# HIVE_BOARD_DECAWAVE.net
KiCad netlist of a schematic drawn in Altium Designer
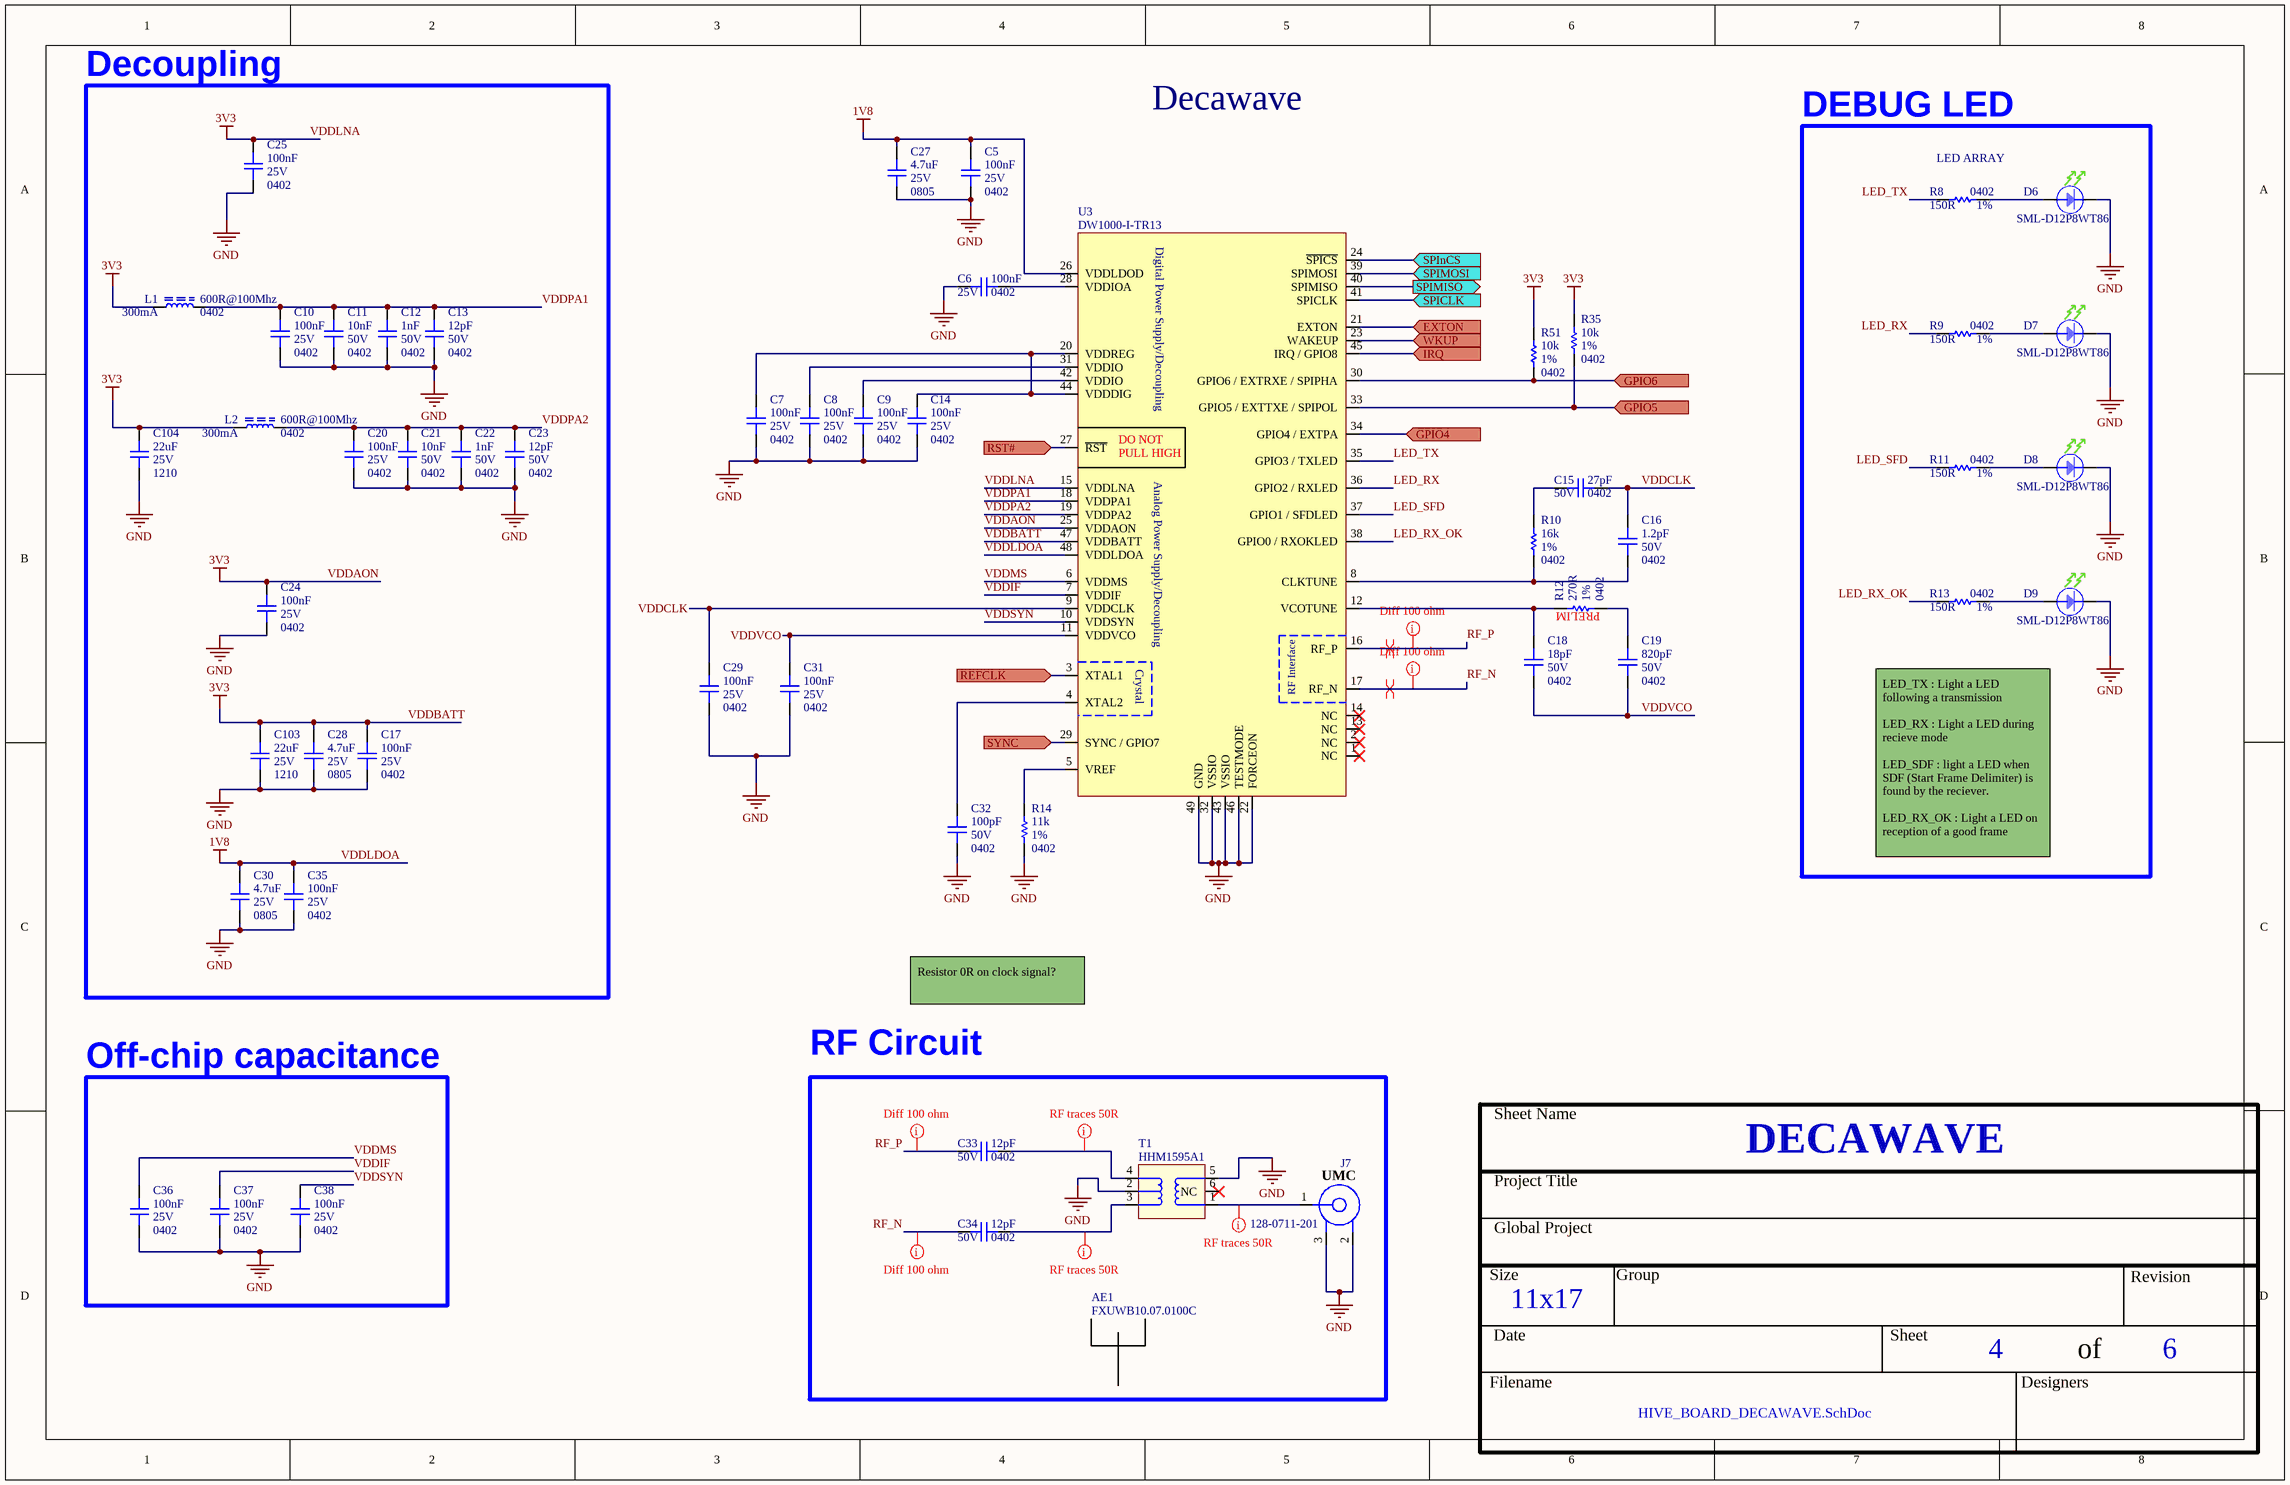
[diagram p0: HIVE_BOARD_DECAWAVE.SchDoc]

(export (version "E")
  (design (tool "Eeschema 10.0.6"))
  (components
    (comp (ref "AE1")
      (value "FXUWB10.07.0100C")
      (description "External antenna - UWB - UMCC plug")
      (fields (field (name "CREATEDBY/DATE") "Philippe Arsenault"))
      (libsource (lib "SWARMUS_LIB") (part "ANT_FXUWB10.07.0100C"))
    )
    (comp (ref "C5")
      (value "100nF")
      (footprint "GRAMS_MASTER_LIB_PCB:CAP_CER_0402")
      (description "CAP - CER 0.1µF 10% 25V X7R - 0402")
      (fields
        (field (name "TOLERANCE") "10%")
        (field (name "PACKAGE") "0402")
        (field (name "VOLTAGE RATING") "25V")
        (field (name "Comment") "CGA2B3X7R1E104K050BB")
        (field (name "CREATEDBY/DATE") "Nicolas Roy 2018-11-07")
        (field (name "VERIFIEDBY") "Nicolas V. (2019-01-22)")
      )
      (libsource (lib "GRAMS_MASTER_LIB_SCH") (part "CAP_CER_CGA2B3X7R1E104K050BB"))
    )
    (comp (ref "C6")
      (value "100nF")
      (footprint "GRAMS_MASTER_LIB_PCB:CAP_CER_0402")
      (description "CAP - CER 0.1µF 10% 25V X7R - 0402")
      (fields
        (field (name "TOLERANCE") "10%")
        (field (name "PACKAGE") "0402")
        (field (name "VOLTAGE RATING") "25V")
        (field (name "Comment") "CGA2B3X7R1E104K050BB")
        (field (name "CREATEDBY/DATE") "Nicolas Roy 2018-11-07")
        (field (name "VERIFIEDBY") "Nicolas V. (2019-01-22)")
      )
      (libsource (lib "GRAMS_MASTER_LIB_SCH") (part "CAP_CER_CGA2B3X7R1E104K050BB"))
    )
    (comp (ref "C7")
      (value "100nF")
      (footprint "GRAMS_MASTER_LIB_PCB:CAP_CER_0402")
      (description "CAP - CER 0.1µF 10% 25V X7R - 0402")
      (fields
        (field (name "TOLERANCE") "10%")
        (field (name "PACKAGE") "0402")
        (field (name "VOLTAGE RATING") "25V")
        (field (name "Comment") "CGA2B3X7R1E104K050BB")
        (field (name "CREATEDBY/DATE") "Nicolas Roy 2018-11-07")
        (field (name "VERIFIEDBY") "Nicolas V. (2019-01-22)")
      )
      (libsource (lib "GRAMS_MASTER_LIB_SCH") (part "CAP_CER_CGA2B3X7R1E104K050BB"))
    )
    (comp (ref "C8")
      (value "100nF")
      (footprint "GRAMS_MASTER_LIB_PCB:CAP_CER_0402")
      (description "CAP - CER 0.1µF 10% 25V X7R - 0402")
      (fields
        (field (name "TOLERANCE") "10%")
        (field (name "PACKAGE") "0402")
        (field (name "VOLTAGE RATING") "25V")
        (field (name "Comment") "CGA2B3X7R1E104K050BB")
        (field (name "CREATEDBY/DATE") "Nicolas Roy 2018-11-07")
        (field (name "VERIFIEDBY") "Nicolas V. (2019-01-22)")
      )
      (libsource (lib "GRAMS_MASTER_LIB_SCH") (part "CAP_CER_CGA2B3X7R1E104K050BB"))
    )
    (comp (ref "C9")
      (value "100nF")
      (footprint "GRAMS_MASTER_LIB_PCB:CAP_CER_0402")
      (description "CAP - CER 0.1µF 10% 25V X7R - 0402")
      (fields
        (field (name "TOLERANCE") "10%")
        (field (name "PACKAGE") "0402")
        (field (name "VOLTAGE RATING") "25V")
        (field (name "Comment") "CGA2B3X7R1E104K050BB")
        (field (name "CREATEDBY/DATE") "Nicolas Roy 2018-11-07")
        (field (name "VERIFIEDBY") "Nicolas V. (2019-01-22)")
      )
      (libsource (lib "GRAMS_MASTER_LIB_SCH") (part "CAP_CER_CGA2B3X7R1E104K050BB"))
    )
    (comp (ref "C10")
      (value "100nF")
      (footprint "GRAMS_MASTER_LIB_PCB:CAP_CER_0402")
      (description "CAP - CER 0.1µF 10% 25V X7R - 0402")
      (fields
        (field (name "TOLERANCE") "10%")
        (field (name "PACKAGE") "0402")
        (field (name "VOLTAGE RATING") "25V")
        (field (name "Comment") "CGA2B3X7R1E104K050BB")
        (field (name "CREATEDBY/DATE") "Nicolas Roy 2018-11-07")
        (field (name "VERIFIEDBY") "Nicolas V. (2019-01-22)")
      )
      (libsource (lib "GRAMS_MASTER_LIB_SCH") (part "CAP_CER_CGA2B3X7R1E104K050BB"))
    )
    (comp (ref "C11")
      (value "10nF")
      (footprint "GRAMS_MASTER_LIB_PCB:CAP_CER_0402")
      (description "CAP - CER 10nF ±10% 50V X7R - 0402")
      (fields
        (field (name "TOLERANCE") "10%")
        (field (name "PACKAGE") "0402")
        (field (name "VOLTAGE RATING") "50V")
        (field (name "Comment") "CL05B103KB5NFNC")
        (field (name "CREATEDBY/DATE") "Keven Deslandes - 2018/11/20")
        (field (name "VERIFIEDBY") "Nicolas Roy - 2018/12/11")
      )
      (libsource (lib "GRAMS_MASTER_LIB_SCH") (part "CAP_CER_CL05B103KB5NFNC"))
    )
    (comp (ref "C12")
      (value "1nF")
      (footprint "CAP_CER_0402")
      (description "CAP - CER 1nF 10% 50V X7R - 0402")
      (fields
        (field (name "TOLERANCE") "10%")
        (field (name "PACKAGE") "0402")
        (field (name "VOLTAGE RATING") "50V")
        (field (name "Comment") "CC0402KRX7R9BB102")
        (field (name "CREATEDBY/DATE") "Jonathan Bouchard 2019-04-06")
        (field (name "VERIFIEDBY") "Nicolas V. (2019-04-30)")
      )
      (libsource (lib "GRAMS_MASTER_LIB_SCH") (part "CAP_CER_CC0402KRX7R9BB102"))
    )
    (comp (ref "C13")
      (value "12pF")
      (footprint "SWARMUS_LIB:CAP_CER_0402")
      (description "CAP - CER 12pF 50V ±5% C0G, NP0 - 0402")
      (fields
        (field (name "TOLERANCE") "±5%")
        (field (name "PACKAGE") "0402")
        (field (name "VOLTAGE RATING") "50V")
        (field (name "Comment") "CC0402JRNPO9BN120")
        (field (name "CREATEDBY/DATE") "Philippe Arsenault/ 2020-07-24")
        (field (name "VERIFIEDBY") "Louis-Daniel Gaulin / 2020-07-29")
      )
      (libsource (lib "SWARMUS_LIB") (part "CAP_CER_CC0402JRNPO9BN120"))
    )
    (comp (ref "C14")
      (value "100nF")
      (footprint "GRAMS_MASTER_LIB_PCB:CAP_CER_0402")
      (description "CAP - CER 0.1µF 10% 25V X7R - 0402")
      (fields
        (field (name "TOLERANCE") "10%")
        (field (name "PACKAGE") "0402")
        (field (name "VOLTAGE RATING") "25V")
        (field (name "Comment") "CGA2B3X7R1E104K050BB")
        (field (name "CREATEDBY/DATE") "Nicolas Roy 2018-11-07")
        (field (name "VERIFIEDBY") "Nicolas V. (2019-01-22)")
      )
      (libsource (lib "GRAMS_MASTER_LIB_SCH") (part "CAP_CER_CGA2B3X7R1E104K050BB"))
    )
    (comp (ref "C15")
      (value "27pF")
      (footprint "SWARMUS_LIB:CAP_CER_0402")
      (description "CAP - CER 27pF 50V ±5% C0G, NP0 - 0402")
      (fields
        (field (name "TOLERANCE") "±5%")
        (field (name "PACKAGE") "0402")
        (field (name "VOLTAGE RATING") "50V")
        (field (name "Comment") "CC0402JRNPO9BN270")
        (field (name "CREATEDBY/DATE") "Philippe Arsenault/ 2020-07-24")
        (field (name "VERIFIEDBY") "Louis-Daniel Gaulin / 2020-07-29")
      )
      (libsource (lib "SWARMUS_LIB") (part "CAP_CER_CC0402JRNPO9BN270"))
    )
    (comp (ref "C16")
      (value "1.2pF")
      (footprint "SWARMUS_LIB:CAP_CER_0402")
      (description "CAP - CER 1.2pF 50V ±0.25pF C0G, NP0 - 0402")
      (fields
        (field (name "TOLERANCE") "±0.25pF")
        (field (name "PACKAGE") "0402")
        (field (name "VOLTAGE RATING") "50V")
        (field (name "Comment") "C0402C129C5GACTU")
        (field (name "CREATEDBY/DATE") "Philippe Arsenault/ 2020-07-24")
        (field (name "VERIFIEDBY") "Louis-Daniel Gaulin / 2020-07-29")
      )
      (libsource (lib "SWARMUS_LIB") (part "CAP_CER_C0402C129C5GACTU"))
    )
    (comp (ref "C17")
      (value "100nF")
      (footprint "GRAMS_MASTER_LIB_PCB:CAP_CER_0402")
      (description "CAP - CER 0.1µF 10% 25V X7R - 0402")
      (fields
        (field (name "TOLERANCE") "10%")
        (field (name "PACKAGE") "0402")
        (field (name "VOLTAGE RATING") "25V")
        (field (name "Comment") "CGA2B3X7R1E104K050BB")
        (field (name "CREATEDBY/DATE") "Nicolas Roy 2018-11-07")
        (field (name "VERIFIEDBY") "Nicolas V. (2019-01-22)")
      )
      (libsource (lib "GRAMS_MASTER_LIB_SCH") (part "CAP_CER_CGA2B3X7R1E104K050BB"))
    )
    (comp (ref "C18")
      (value "18pF")
      (footprint "CAP_CER_0402")
      (description "CAP - CER 18pF 50V C0G, NPO - 0402")
      (fields
        (field (name "TOLERANCE") "2%")
        (field (name "PACKAGE") "0402")
        (field (name "VOLTAGE RATING") "50V")
        (field (name "Comment") "GRM1555C1H180GA01D")
        (field (name "CREATEDBY/DATE") "Tommy Rossignol / 2018-11-20")
        (field (name "VERIFIEDBY") "Caroline Paulin - 13 fév 2019")
      )
      (libsource (lib "GRAMS_MASTER_LIB_SCH") (part "CAP_CER_GRM1555C1H180GA01D"))
    )
    (comp (ref "C19")
      (value "820pF")
      (footprint "SWARMUS_LIB:CAP_CER_0402")
      (description "CAP - CER 820pF 50V ±10% X7R - 0402")
      (fields
        (field (name "TOLERANCE") "±10%")
        (field (name "PACKAGE") "0402")
        (field (name "VOLTAGE RATING") "50V")
        (field (name "Comment") "CC0402KRX7R9BB821")
        (field (name "CREATEDBY/DATE") "Philippe Arsenault/ 2020-07-24")
        (field (name "VERIFIEDBY") "Louis-Daniel Gaulin / 2020-07-29")
      )
      (libsource (lib "SWARMUS_LIB") (part "CAP_CER_CC0402KRX7R9BB821"))
    )
    (comp (ref "C20")
      (value "100nF")
      (footprint "GRAMS_MASTER_LIB_PCB:CAP_CER_0402")
      (description "CAP - CER 0.1µF 10% 25V X7R - 0402")
      (fields
        (field (name "TOLERANCE") "10%")
        (field (name "PACKAGE") "0402")
        (field (name "VOLTAGE RATING") "25V")
        (field (name "Comment") "CGA2B3X7R1E104K050BB")
        (field (name "CREATEDBY/DATE") "Nicolas Roy 2018-11-07")
        (field (name "VERIFIEDBY") "Nicolas V. (2019-01-22)")
      )
      (libsource (lib "GRAMS_MASTER_LIB_SCH") (part "CAP_CER_CGA2B3X7R1E104K050BB"))
    )
    (comp (ref "C21")
      (value "10nF")
      (footprint "GRAMS_MASTER_LIB_PCB:CAP_CER_0402")
      (description "CAP - CER 10nF ±10% 50V X7R - 0402")
      (fields
        (field (name "TOLERANCE") "10%")
        (field (name "PACKAGE") "0402")
        (field (name "VOLTAGE RATING") "50V")
        (field (name "Comment") "CL05B103KB5NFNC")
        (field (name "CREATEDBY/DATE") "Keven Deslandes - 2018/11/20")
        (field (name "VERIFIEDBY") "Nicolas Roy - 2018/12/11")
      )
      (libsource (lib "GRAMS_MASTER_LIB_SCH") (part "CAP_CER_CL05B103KB5NFNC"))
    )
    (comp (ref "C22")
      (value "1nF")
      (footprint "CAP_CER_0402")
      (description "CAP - CER 1nF 10% 50V X7R - 0402")
      (fields
        (field (name "TOLERANCE") "10%")
        (field (name "PACKAGE") "0402")
        (field (name "VOLTAGE RATING") "50V")
        (field (name "Comment") "CC0402KRX7R9BB102")
        (field (name "CREATEDBY/DATE") "Jonathan Bouchard 2019-04-06")
        (field (name "VERIFIEDBY") "Nicolas V. (2019-04-30)")
      )
      (libsource (lib "GRAMS_MASTER_LIB_SCH") (part "CAP_CER_CC0402KRX7R9BB102"))
    )
    (comp (ref "C23")
      (value "12pF")
      (footprint "SWARMUS_LIB:CAP_CER_0402")
      (description "CAP - CER 12pF 50V ±5% C0G, NP0 - 0402")
      (fields
        (field (name "TOLERANCE") "±5%")
        (field (name "PACKAGE") "0402")
        (field (name "VOLTAGE RATING") "50V")
        (field (name "Comment") "CC0402JRNPO9BN120")
        (field (name "CREATEDBY/DATE") "Philippe Arsenault/ 2020-07-24")
        (field (name "VERIFIEDBY") "Louis-Daniel Gaulin / 2020-07-29")
      )
      (libsource (lib "SWARMUS_LIB") (part "CAP_CER_CC0402JRNPO9BN120"))
    )
    (comp (ref "C24")
      (value "100nF")
      (footprint "GRAMS_MASTER_LIB_PCB:CAP_CER_0402")
      (description "CAP - CER 0.1µF 10% 25V X7R - 0402")
      (fields
        (field (name "TOLERANCE") "10%")
        (field (name "PACKAGE") "0402")
        (field (name "VOLTAGE RATING") "25V")
        (field (name "Comment") "CGA2B3X7R1E104K050BB")
        (field (name "CREATEDBY/DATE") "Nicolas Roy 2018-11-07")
        (field (name "VERIFIEDBY") "Nicolas V. (2019-01-22)")
      )
      (libsource (lib "GRAMS_MASTER_LIB_SCH") (part "CAP_CER_CGA2B3X7R1E104K050BB"))
    )
    (comp (ref "C25")
      (value "100nF")
      (footprint "GRAMS_MASTER_LIB_PCB:CAP_CER_0402")
      (description "CAP - CER 0.1µF 10% 25V X7R - 0402")
      (fields
        (field (name "TOLERANCE") "10%")
        (field (name "PACKAGE") "0402")
        (field (name "VOLTAGE RATING") "25V")
        (field (name "Comment") "CGA2B3X7R1E104K050BB")
        (field (name "CREATEDBY/DATE") "Nicolas Roy 2018-11-07")
        (field (name "VERIFIEDBY") "Nicolas V. (2019-01-22)")
      )
      (libsource (lib "GRAMS_MASTER_LIB_SCH") (part "CAP_CER_CGA2B3X7R1E104K050BB"))
    )
    (comp (ref "C27")
      (value "4.7uF")
      (footprint "GRAMS_MASTER_LIB_PCB:CAP_CER_0805")
      (description "CAP - CER 4.7UF 10% 25V X7R - 0805")
      (fields
        (field (name "TOLERANCE") "10%")
        (field (name "PACKAGE") "0805")
        (field (name "VOLTAGE RATING") "25V")
        (field (name "Comment") "C2012X7R1E475K125AE")
        (field (name "CREATEDBY/DATE") "Keven Deslandes - 2018/11/09")
        (field (name "VERIFIEDBY") "Nicolas Roy - 2018/12/11")
      )
      (libsource (lib "GRAMS_MASTER_LIB_SCH") (part "CAP_CER_C2012X7R1E475K125AE"))
    )
    (comp (ref "C28")
      (value "4.7uF")
      (footprint "GRAMS_MASTER_LIB_PCB:CAP_CER_0805")
      (description "CAP - CER 4.7UF 10% 25V X7R - 0805")
      (fields
        (field (name "TOLERANCE") "10%")
        (field (name "PACKAGE") "0805")
        (field (name "VOLTAGE RATING") "25V")
        (field (name "Comment") "C2012X7R1E475K125AE")
        (field (name "CREATEDBY/DATE") "Keven Deslandes - 2018/11/09")
        (field (name "VERIFIEDBY") "Nicolas Roy - 2018/12/11")
      )
      (libsource (lib "GRAMS_MASTER_LIB_SCH") (part "CAP_CER_C2012X7R1E475K125AE"))
    )
    (comp (ref "C29")
      (value "100nF")
      (footprint "GRAMS_MASTER_LIB_PCB:CAP_CER_0402")
      (description "CAP - CER 0.1µF 10% 25V X7R - 0402")
      (fields
        (field (name "TOLERANCE") "10%")
        (field (name "PACKAGE") "0402")
        (field (name "VOLTAGE RATING") "25V")
        (field (name "Comment") "CGA2B3X7R1E104K050BB")
        (field (name "CREATEDBY/DATE") "Nicolas Roy 2018-11-07")
        (field (name "VERIFIEDBY") "Nicolas V. (2019-01-22)")
      )
      (libsource (lib "GRAMS_MASTER_LIB_SCH") (part "CAP_CER_CGA2B3X7R1E104K050BB"))
    )
    (comp (ref "C30")
      (value "4.7uF")
      (footprint "GRAMS_MASTER_LIB_PCB:CAP_CER_0805")
      (description "CAP - CER 4.7UF 10% 25V X7R - 0805")
      (fields
        (field (name "TOLERANCE") "10%")
        (field (name "PACKAGE") "0805")
        (field (name "VOLTAGE RATING") "25V")
        (field (name "Comment") "C2012X7R1E475K125AE")
        (field (name "CREATEDBY/DATE") "Keven Deslandes - 2018/11/09")
        (field (name "VERIFIEDBY") "Nicolas Roy - 2018/12/11")
      )
      (libsource (lib "GRAMS_MASTER_LIB_SCH") (part "CAP_CER_C2012X7R1E475K125AE"))
    )
    (comp (ref "C31")
      (value "100nF")
      (footprint "GRAMS_MASTER_LIB_PCB:CAP_CER_0402")
      (description "CAP - CER 0.1µF 10% 25V X7R - 0402")
      (fields
        (field (name "TOLERANCE") "10%")
        (field (name "PACKAGE") "0402")
        (field (name "VOLTAGE RATING") "25V")
        (field (name "Comment") "CGA2B3X7R1E104K050BB")
        (field (name "CREATEDBY/DATE") "Nicolas Roy 2018-11-07")
        (field (name "VERIFIEDBY") "Nicolas V. (2019-01-22)")
      )
      (libsource (lib "GRAMS_MASTER_LIB_SCH") (part "CAP_CER_CGA2B3X7R1E104K050BB"))
    )
    (comp (ref "C32")
      (value "100pF")
      (footprint "SWARMUS_LIB:CAP_CER_0402")
      (description "CAP - CER 100pF 50V ±5% C0G,CP0 - 0402")
      (fields
        (field (name "TOLERANCE") "±5%")
        (field (name "PACKAGE") "0402")
        (field (name "VOLTAGE RATING") "50V")
        (field (name "Comment") "CC0402JRNPO9BN101")
        (field (name "CREATEDBY/DATE") "Philippe Arsenault/ 2020-07-24")
        (field (name "VERIFIEDBY") "Louis-Daniel Gaulin / 2020-07-29")
      )
      (libsource (lib "SWARMUS_LIB") (part "CAP_CER_CC0402JRNPO9BN101"))
    )
    (comp (ref "C33")
      (value "12pF")
      (footprint "SWARMUS_LIB:CAP_CER_0402")
      (description "CAP - CER 12pF 50V ±5% C0G, NP0 - 0402")
      (fields
        (field (name "TOLERANCE") "±5%")
        (field (name "PACKAGE") "0402")
        (field (name "VOLTAGE RATING") "50V")
        (field (name "Comment") "CC0402JRNPO9BN120")
        (field (name "CREATEDBY/DATE") "Philippe Arsenault/ 2020-07-24")
        (field (name "VERIFIEDBY") "Louis-Daniel Gaulin / 2020-07-29")
      )
      (libsource (lib "SWARMUS_LIB") (part "CAP_CER_CC0402JRNPO9BN120"))
    )
    (comp (ref "C34")
      (value "12pF")
      (footprint "SWARMUS_LIB:CAP_CER_0402")
      (description "CAP - CER 12pF 50V ±5% C0G, NP0 - 0402")
      (fields
        (field (name "TOLERANCE") "±5%")
        (field (name "PACKAGE") "0402")
        (field (name "VOLTAGE RATING") "50V")
        (field (name "Comment") "CC0402JRNPO9BN120")
        (field (name "CREATEDBY/DATE") "Philippe Arsenault/ 2020-07-24")
        (field (name "VERIFIEDBY") "Louis-Daniel Gaulin / 2020-07-29")
      )
      (libsource (lib "SWARMUS_LIB") (part "CAP_CER_CC0402JRNPO9BN120"))
    )
    (comp (ref "C35")
      (value "100nF")
      (footprint "GRAMS_MASTER_LIB_PCB:CAP_CER_0402")
      (description "CAP - CER 0.1µF 10% 25V X7R - 0402")
      (fields
        (field (name "TOLERANCE") "10%")
        (field (name "PACKAGE") "0402")
        (field (name "VOLTAGE RATING") "25V")
        (field (name "Comment") "CGA2B3X7R1E104K050BB")
        (field (name "CREATEDBY/DATE") "Nicolas Roy 2018-11-07")
        (field (name "VERIFIEDBY") "Nicolas V. (2019-01-22)")
      )
      (libsource (lib "GRAMS_MASTER_LIB_SCH") (part "CAP_CER_CGA2B3X7R1E104K050BB"))
    )
    (comp (ref "C36")
      (value "100nF")
      (footprint "GRAMS_MASTER_LIB_PCB:CAP_CER_0402")
      (description "CAP - CER 0.1µF 10% 25V X7R - 0402")
      (fields
        (field (name "TOLERANCE") "10%")
        (field (name "PACKAGE") "0402")
        (field (name "VOLTAGE RATING") "25V")
        (field (name "Comment") "CGA2B3X7R1E104K050BB")
        (field (name "CREATEDBY/DATE") "Nicolas Roy 2018-11-07")
        (field (name "VERIFIEDBY") "Nicolas V. (2019-01-22)")
      )
      (libsource (lib "GRAMS_MASTER_LIB_SCH") (part "CAP_CER_CGA2B3X7R1E104K050BB"))
    )
    (comp (ref "C37")
      (value "100nF")
      (footprint "GRAMS_MASTER_LIB_PCB:CAP_CER_0402")
      (description "CAP - CER 0.1µF 10% 25V X7R - 0402")
      (fields
        (field (name "TOLERANCE") "10%")
        (field (name "PACKAGE") "0402")
        (field (name "VOLTAGE RATING") "25V")
        (field (name "Comment") "CGA2B3X7R1E104K050BB")
        (field (name "CREATEDBY/DATE") "Nicolas Roy 2018-11-07")
        (field (name "VERIFIEDBY") "Nicolas V. (2019-01-22)")
      )
      (libsource (lib "GRAMS_MASTER_LIB_SCH") (part "CAP_CER_CGA2B3X7R1E104K050BB"))
    )
    (comp (ref "C38")
      (value "100nF")
      (footprint "GRAMS_MASTER_LIB_PCB:CAP_CER_0402")
      (description "CAP - CER 0.1µF 10% 25V X7R - 0402")
      (fields
        (field (name "TOLERANCE") "10%")
        (field (name "PACKAGE") "0402")
        (field (name "VOLTAGE RATING") "25V")
        (field (name "Comment") "CGA2B3X7R1E104K050BB")
        (field (name "CREATEDBY/DATE") "Nicolas Roy 2018-11-07")
        (field (name "VERIFIEDBY") "Nicolas V. (2019-01-22)")
      )
      (libsource (lib "GRAMS_MASTER_LIB_SCH") (part "CAP_CER_CGA2B3X7R1E104K050BB"))
    )
    (comp (ref "C103")
      (value "22uF")
      (footprint "GRAMS_MASTER_LIB_PCB:CAP_CER_1210")
      (description "CAP - CER 22UF 20% 25V X7R - 1210")
      (fields
        (field (name "TOLERANCE") "20%")
        (field (name "PACKAGE") "1210")
        (field (name "VOLTAGE RATING") "25V")
        (field (name "Comment") "C3225X7R1E226M250AB")
        (field (name "CREATEDBY/DATE") "Nicolas V. (2019-12-11)")
        (field (name "VERIFIEDBY") "Nicolas V. (2019-12-11)")
      )
      (libsource (lib "GRAMS_MASTER_LIB_SCH") (part "CAP_CER_C3225X7R1E226M250AB"))
    )
    (comp (ref "C104")
      (value "22uF")
      (footprint "GRAMS_MASTER_LIB_PCB:CAP_CER_1210")
      (description "CAP - CER 22UF 20% 25V X7R - 1210")
      (fields
        (field (name "TOLERANCE") "20%")
        (field (name "PACKAGE") "1210")
        (field (name "VOLTAGE RATING") "25V")
        (field (name "Comment") "C3225X7R1E226M250AB")
        (field (name "CREATEDBY/DATE") "Nicolas V. (2019-12-11)")
        (field (name "VERIFIEDBY") "Nicolas V. (2019-12-11)")
      )
      (libsource (lib "GRAMS_MASTER_LIB_SCH") (part "CAP_CER_C3225X7R1E226M250AB"))
    )
    (comp (ref "D6")
      (value "SML-D12P8WT86")
      (footprint "GRAMS_MASTER_LIB_PCB:LED_SML-D12P8WT86")
      (description "LED - GREEN DIFFUSED 0603 SMD - 0603")
      (fields
        (field (name "CREATEDBY/DATE") "Keven Deslandes - 2018/11/21")
        (field (name "VERIFIEDBY") "Caroline Paulin - 13 février 2019")
      )
      (libsource (lib "GRAMS_MASTER_LIB_SCH") (part "LED_SML-D12P8WT86"))
    )
    (comp (ref "D7")
      (value "SML-D12P8WT86")
      (footprint "GRAMS_MASTER_LIB_PCB:LED_SML-D12P8WT86")
      (description "LED - GREEN DIFFUSED 0603 SMD - 0603")
      (fields
        (field (name "CREATEDBY/DATE") "Keven Deslandes - 2018/11/21")
        (field (name "VERIFIEDBY") "Caroline Paulin - 13 février 2019")
      )
      (libsource (lib "GRAMS_MASTER_LIB_SCH") (part "LED_SML-D12P8WT86"))
    )
    (comp (ref "D8")
      (value "SML-D12P8WT86")
      (footprint "GRAMS_MASTER_LIB_PCB:LED_SML-D12P8WT86")
      (description "LED - GREEN DIFFUSED 0603 SMD - 0603")
      (fields
        (field (name "CREATEDBY/DATE") "Keven Deslandes - 2018/11/21")
        (field (name "VERIFIEDBY") "Caroline Paulin - 13 février 2019")
      )
      (libsource (lib "GRAMS_MASTER_LIB_SCH") (part "LED_SML-D12P8WT86"))
    )
    (comp (ref "D9")
      (value "SML-D12P8WT86")
      (footprint "GRAMS_MASTER_LIB_PCB:LED_SML-D12P8WT86")
      (description "LED - GREEN DIFFUSED 0603 SMD - 0603")
      (fields
        (field (name "CREATEDBY/DATE") "Keven Deslandes - 2018/11/21")
        (field (name "VERIFIEDBY") "Caroline Paulin - 13 février 2019")
      )
      (libsource (lib "GRAMS_MASTER_LIB_SCH") (part "LED_SML-D12P8WT86"))
    )
    (comp (ref "J7")
      (value "128-0711-201")
      (footprint "GRAMS_MASTER_LIB_PCB:CON_UMC_128-0711-201")
      (description "CON - UMC JACK STR 50 OHM - SMD")
      (fields
        (field (name "CREATEDBY/DATE") "Keven Desandes - 2018/09/27")
        (field (name "VERIFIEDBY") "Caroline Paulin - 23 janv 2019")
      )
      (libsource (lib "GRAMS_MASTER_LIB_SCH") (part "CON_UMC_128-0711-201"))
    )
    (comp (ref "L1")
      (value "600R@100Mhz")
      (footprint "FER_0402")
      (description "FER - FERRITE BEAD 600 OHM@100MHz - 0402")
      (fields
        (field (name "CURRENT RATING") "300mA")
        (field (name "PACKAGE") "0402")
        (field (name "Comment") "BLM15AG601SN1D")
        (field (name "CREATEDBY/DATE") "Philippe Arsenault/2020-07-24")
      )
      (libsource (lib "a_Valider_PA") (part "FER_BLM15AG601SN1D"))
    )
    (comp (ref "L2")
      (value "600R@100Mhz")
      (footprint "FER_0402")
      (description "FER - FERRITE BEAD 600 OHM@100MHz - 0402")
      (fields
        (field (name "CURRENT RATING") "300mA")
        (field (name "PACKAGE") "0402")
        (field (name "Comment") "BLM15AG601SN1D")
        (field (name "CREATEDBY/DATE") "Philippe Arsenault/2020-07-24")
      )
      (libsource (lib "a_Valider_PA") (part "FER_BLM15AG601SN1D"))
    )
    (comp (ref "R8")
      (value "150R")
      (footprint "RES_0402")
      (description "RES - 150R 1% 1/16W - 0402")
      (fields
        (field (name "TOLERANCE") "1%")
        (field (name "PACKAGE") "0402")
        (field (name "Comment") "RC0402FR-07150RL")
        (field (name "CREATEDBY/DATE") "Jonathan Bouchard 2019-03-25")
        (field (name "VERIFIEDBY") "Nicolas V. (2019-05-02)")
      )
      (libsource (lib "GRAMS_MASTER_LIB_SCH") (part "RES_RC0402FR-07150RL"))
    )
    (comp (ref "R9")
      (value "150R")
      (footprint "RES_0402")
      (description "RES - 150R 1% 1/16W - 0402")
      (fields
        (field (name "TOLERANCE") "1%")
        (field (name "PACKAGE") "0402")
        (field (name "Comment") "RC0402FR-07150RL")
        (field (name "CREATEDBY/DATE") "Jonathan Bouchard 2019-03-25")
        (field (name "VERIFIEDBY") "Nicolas V. (2019-05-02)")
      )
      (libsource (lib "GRAMS_MASTER_LIB_SCH") (part "RES_RC0402FR-07150RL"))
    )
    (comp (ref "R10")
      (value "16k")
      (footprint "GRAMS_MASTER_LIB_PCB:RES_0402")
      (description "RES - 16k OHM 1% 1/16W - 0402")
      (fields
        (field (name "TOLERANCE") "1%")
        (field (name "PACKAGE") "0402")
        (field (name "Comment") "RC0402FR-0716KL")
        (field (name "CREATEDBY/DATE") "Nicolas Roy/18 oct. 2018")
        (field (name "VERIFIEDBY") "Caroline Paulin - 18/12/2018")
      )
      (libsource (lib "GRAMS_MASTER_LIB_SCH") (part "RES_RC0402FR-0716KL"))
    )
    (comp (ref "R11")
      (value "150R")
      (footprint "RES_0402")
      (description "RES - 150R 1% 1/16W - 0402")
      (fields
        (field (name "TOLERANCE") "1%")
        (field (name "PACKAGE") "0402")
        (field (name "Comment") "RC0402FR-07150RL")
        (field (name "CREATEDBY/DATE") "Jonathan Bouchard 2019-03-25")
        (field (name "VERIFIEDBY") "Nicolas V. (2019-05-02)")
      )
      (libsource (lib "GRAMS_MASTER_LIB_SCH") (part "RES_RC0402FR-07150RL"))
    )
    (comp (ref "R12")
      (value "270R")
      (footprint "RES_0402")
      (description "RES - 270 Ohms ±1% 0.063W, 1/16W Chip Resistor 0402  (1005 Metric)")
      (fields
        (field (name "TOLERANCE") "1%")
        (field (name "PACKAGE") "0402")
        (field (name "Comment") "RC0402FR-07270RL")
        (field (name "CREATEDBY/DATE") "Philippe Arsenault/2021-02-08")
      )
      (libsource (lib "a_Valider_HD") (part "RES_RC0402FR-07270RL"))
    )
    (comp (ref "R13")
      (value "150R")
      (footprint "RES_0402")
      (description "RES - 150R 1% 1/16W - 0402")
      (fields
        (field (name "TOLERANCE") "1%")
        (field (name "PACKAGE") "0402")
        (field (name "Comment") "RC0402FR-07150RL")
        (field (name "CREATEDBY/DATE") "Jonathan Bouchard 2019-03-25")
        (field (name "VERIFIEDBY") "Nicolas V. (2019-05-02)")
      )
      (libsource (lib "GRAMS_MASTER_LIB_SCH") (part "RES_RC0402FR-07150RL"))
    )
    (comp (ref "R14")
      (value "11k")
      (footprint "GRAMS_MASTER_LIB_PCB:RES_0402")
      (description "RES - 11K 1% 1/16W - 0402")
      (fields
        (field (name "TOLERANCE") "1%")
        (field (name "PACKAGE") "0402")
        (field (name "Comment") "RC0402FR-0711KL")
        (field (name "CREATEDBY/DATE") "Keven Deslandes 2018-10-15")
        (field (name "VERIFIEDBY") "Carolilne Paulin - 18/12/2018")
      )
      (libsource (lib "GRAMS_MASTER_LIB_SCH") (part "RES_RC0402FR-0711KL"))
    )
    (comp (ref "R35")
      (value "10k")
      (footprint "GRAMS_MASTER_LIB_PCB:RES_0402")
      (description "RES - 10K OHM 1% 1/16W - 0402")
      (fields
        (field (name "TOLERANCE") "1%")
        (field (name "PACKAGE") "0402")
        (field (name "Comment") "RC0402FR-0710KP")
        (field (name "CREATEDBY/DATE") "Jonathan Bouchard 2018-07-05")
        (field (name "VERIFIEDBY") "Arnaud Samson 16-07-18")
      )
      (libsource (lib "GRAMS_MASTER_LIB_SCH") (part "RES_RC0402FR-0710KP"))
    )
    (comp (ref "R51")
      (value "10k")
      (footprint "GRAMS_MASTER_LIB_PCB:RES_0402")
      (description "RES - 10K OHM 1% 1/16W - 0402")
      (fields
        (field (name "TOLERANCE") "1%")
        (field (name "PACKAGE") "0402")
        (field (name "Comment") "RC0402FR-0710KP")
        (field (name "CREATEDBY/DATE") "Jonathan Bouchard 2018-07-05")
        (field (name "VERIFIEDBY") "Arnaud Samson 16-07-18")
      )
      (libsource (lib "GRAMS_MASTER_LIB_SCH") (part "RES_RC0402FR-0710KP"))
    )
    (comp (ref "T1")
      (value "HHM1595A1")
      (footprint "XFR_HHM1595A1")
      (description "XFR - Imp Unbalaced/Balanced 50/100 3-8GHz  -SMD")
      (fields
        (field (name "CREATEDBY/DATE") "Philippe Arsenault/2020-21-07")
        (field (name "VERIFIEDBY") "Louis-Daniel Gaulin / 03-10-2020")
      )
      (libsource (lib "SWARMUS_LIB") (part "XFR_HHM1595A1"))
    )
    (comp (ref "U3")
      (value "DW1000-I-TR13")
      (footprint "SWARMUS_LIB:COM_XCV_DW1000-I-TR13")
      (description "COM - IC RF TxRx 802.15.4 IR-UWB DECAWAVE - 48-VFQFN EP")
      (fields (field (name "CREATEDBY/DATE") "Philippe Arsenault/13-07-2020"))
      (libsource (lib "SWARMUS_LIB") (part "COM_XCV_DW1000-I-TR13"))
    )
  )
  (nets
    (net (code "1") (name "/EXTON") (class "Default")
      (node (ref "U3") (pin "21") (pinfunction "EXTON_21") (pintype "passive"))
    )
    (net (code "2") (name "/GPIO4") (class "Default")
      (node (ref "U3") (pin "34") (pinfunction "GPIO4_/_EXTPA_34") (pintype "passive"))
    )
    (net (code "3") (name "/GPIO5") (class "Default")
      (node (ref "R35") (pin "1") (pinfunction "1_1") (pintype "passive"))
      (node (ref "U3") (pin "33") (pinfunction "GPIO5_/_EXTTXE_/_SPIPOL_33") (pintype "passive"))
    )
    (net (code "4") (name "/GPIO6") (class "Default")
      (node (ref "R51") (pin "1") (pinfunction "1_1") (pintype "passive"))
      (node (ref "U3") (pin "30") (pinfunction "GPIO6_/_EXTRXE_/_SPIPHA_30") (pintype "passive"))
    )
    (net (code "5") (name "/IRQ") (class "Default")
      (node (ref "U3") (pin "45") (pinfunction "IRQ_/_GPIO8_45") (pintype "passive"))
    )
    (net (code "6") (name "/LED_RX") (class "Default")
      (node (ref "R9") (pin "2") (pinfunction "2_2") (pintype "passive"))
      (node (ref "U3") (pin "36") (pinfunction "GPIO2_/_RXLED_36") (pintype "passive"))
    )
    (net (code "7") (name "/LED_RX_OK") (class "Default")
      (node (ref "R13") (pin "2") (pinfunction "2_2") (pintype "passive"))
      (node (ref "U3") (pin "38") (pinfunction "GPIO0_/_RXOKLED_38") (pintype "passive"))
    )
    (net (code "8") (name "/LED_SFD") (class "Default")
      (node (ref "R11") (pin "2") (pinfunction "2_2") (pintype "passive"))
      (node (ref "U3") (pin "37") (pinfunction "GPIO1_/_SFDLED_37") (pintype "passive"))
    )
    (net (code "9") (name "/LED_TX") (class "Default")
      (node (ref "R8") (pin "2") (pinfunction "2_2") (pintype "passive"))
      (node (ref "U3") (pin "35") (pinfunction "GPIO3_/_TXLED_35") (pintype "passive"))
    )
    (net (code "10") (name "/REFCLK") (class "Default")
      (node (ref "U3") (pin "3") (pinfunction "XTAL1_3") (pintype "passive"))
    )
    (net (code "11") (name "/RF_N") (class "Default")
      (node (ref "C34") (pin "2") (pinfunction "2_2") (pintype "passive"))
      (node (ref "U3") (pin "17") (pinfunction "RF_N_17") (pintype "passive"))
    )
    (net (code "12") (name "/RF_P") (class "Default")
      (node (ref "C33") (pin "2") (pinfunction "2_2") (pintype "passive"))
      (node (ref "U3") (pin "16") (pinfunction "RF_P_16") (pintype "passive"))
    )
    (net (code "13") (name "/RST#") (class "Default")
      (node (ref "U3") (pin "27") (pinfunction "RST_27") (pintype "passive"))
    )
    (net (code "14") (name "/SPICLK") (class "Default")
      (node (ref "U3") (pin "41") (pinfunction "SPICLK_41") (pintype "passive"))
    )
    (net (code "15") (name "/SPIMISO") (class "Default")
      (node (ref "U3") (pin "40") (pinfunction "SPIMISO_40") (pintype "passive"))
    )
    (net (code "16") (name "/SPIMOSI") (class "Default")
      (node (ref "U3") (pin "39") (pinfunction "SPIMOSI_39") (pintype "passive"))
    )
    (net (code "17") (name "/SPInCS") (class "Default")
      (node (ref "U3") (pin "24") (pinfunction "SPICS_24") (pintype "passive"))
    )
    (net (code "18") (name "/SYNC") (class "Default")
      (node (ref "U3") (pin "29") (pinfunction "SYNC_/_GPIO7_29") (pintype "passive"))
    )
    (net (code "19") (name "/VDDCLK") (class "Default")
      (node (ref "C15") (pin "1") (pinfunction "1_1") (pintype "passive"))
      (node (ref "C16") (pin "2") (pinfunction "2_2") (pintype "passive"))
      (node (ref "C29") (pin "2") (pinfunction "2_2") (pintype "passive"))
      (node (ref "U3") (pin "9") (pinfunction "VDDCLK_9") (pintype "passive"))
    )
    (net (code "20") (name "/VDDIF") (class "Default")
      (node (ref "C37") (pin "2") (pinfunction "2_2") (pintype "passive"))
      (node (ref "U3") (pin "7") (pinfunction "VDDIF_7") (pintype "passive"))
    )
    (net (code "21") (name "/VDDMS") (class "Default")
      (node (ref "C36") (pin "2") (pinfunction "2_2") (pintype "passive"))
      (node (ref "U3") (pin "6") (pinfunction "VDDMS_6") (pintype "passive"))
    )
    (net (code "22") (name "/VDDPA1") (class "Default")
      (node (ref "C10") (pin "2") (pinfunction "2_2") (pintype "passive"))
      (node (ref "C11") (pin "2") (pinfunction "2_2") (pintype "passive"))
      (node (ref "C12") (pin "2") (pinfunction "2_2") (pintype "passive"))
      (node (ref "C13") (pin "2") (pinfunction "2_2") (pintype "passive"))
      (node (ref "L1") (pin "2") (pinfunction "2_2") (pintype "passive"))
      (node (ref "U3") (pin "18") (pinfunction "VDDPA1_18") (pintype "passive"))
    )
    (net (code "23") (name "/VDDPA2") (class "Default")
      (node (ref "C20") (pin "2") (pinfunction "2_2") (pintype "passive"))
      (node (ref "C21") (pin "2") (pinfunction "2_2") (pintype "passive"))
      (node (ref "C22") (pin "2") (pinfunction "2_2") (pintype "passive"))
      (node (ref "C23") (pin "2") (pinfunction "2_2") (pintype "passive"))
      (node (ref "L2") (pin "2") (pinfunction "2_2") (pintype "passive"))
      (node (ref "U3") (pin "19") (pinfunction "VDDPA2_19") (pintype "passive"))
    )
    (net (code "24") (name "/VDDSYN") (class "Default")
      (node (ref "C38") (pin "2") (pinfunction "2_2") (pintype "passive"))
      (node (ref "U3") (pin "10") (pinfunction "VDDSYN_10") (pintype "passive"))
    )
    (net (code "25") (name "/VDDVCO") (class "Default")
      (node (ref "C18") (pin "1") (pinfunction "1_1") (pintype "passive"))
      (node (ref "C19") (pin "1") (pinfunction "1_1") (pintype "passive"))
      (node (ref "C31") (pin "2") (pinfunction "2_2") (pintype "passive"))
      (node (ref "U3") (pin "11") (pinfunction "VDDVCO_11") (pintype "passive"))
    )
    (net (code "26") (name "/WKUP") (class "Default")
      (node (ref "U3") (pin "23") (pinfunction "WAKEUP_23") (pintype "passive"))
    )
    (net (code "27") (name "1V8") (class "Default")
      (node (ref "C27") (pin "2") (pinfunction "2_2") (pintype "passive"))
      (node (ref "C30") (pin "2") (pinfunction "2_2") (pintype "passive"))
      (node (ref "C35") (pin "2") (pinfunction "2_2") (pintype "passive"))
      (node (ref "C5") (pin "2") (pinfunction "2_2") (pintype "passive"))
      (node (ref "U3") (pin "26") (pinfunction "VDDLDOD_26") (pintype "passive"))
      (node (ref "U3") (pin "48") (pinfunction "VDDLDOA_48") (pintype "passive"))
    )
    (net (code "28") (name "3V3") (class "Default")
      (node (ref "C103") (pin "2") (pinfunction "2_2") (pintype "passive"))
      (node (ref "C104") (pin "2") (pinfunction "2_2") (pintype "passive"))
      (node (ref "C17") (pin "2") (pinfunction "2_2") (pintype "passive"))
      (node (ref "C24") (pin "2") (pinfunction "2_2") (pintype "passive"))
      (node (ref "C25") (pin "2") (pinfunction "2_2") (pintype "passive"))
      (node (ref "C28") (pin "2") (pinfunction "2_2") (pintype "passive"))
      (node (ref "L1") (pin "1") (pinfunction "1_1") (pintype "passive"))
      (node (ref "L2") (pin "1") (pinfunction "1_1") (pintype "passive"))
      (node (ref "R35") (pin "2") (pinfunction "2_2") (pintype "passive"))
      (node (ref "R51") (pin "2") (pinfunction "2_2") (pintype "passive"))
      (node (ref "U3") (pin "15") (pinfunction "VDDLNA_15") (pintype "passive"))
      (node (ref "U3") (pin "25") (pinfunction "VDDAON_25") (pintype "passive"))
      (node (ref "U3") (pin "47") (pinfunction "VDDBATT_47") (pintype "passive"))
    )
    (net (code "29") (name "GND") (class "Default")
      (node (ref "C10") (pin "1") (pinfunction "1_1") (pintype "passive"))
      (node (ref "C103") (pin "1") (pinfunction "1_1") (pintype "passive"))
      (node (ref "C104") (pin "1") (pinfunction "1_1") (pintype "passive"))
      (node (ref "C11") (pin "1") (pinfunction "1_1") (pintype "passive"))
      (node (ref "C12") (pin "1") (pinfunction "1_1") (pintype "passive"))
      (node (ref "C13") (pin "1") (pinfunction "1_1") (pintype "passive"))
      (node (ref "C14") (pin "1") (pinfunction "1_1") (pintype "passive"))
      (node (ref "C17") (pin "1") (pinfunction "1_1") (pintype "passive"))
      (node (ref "C20") (pin "1") (pinfunction "1_1") (pintype "passive"))
      (node (ref "C21") (pin "1") (pinfunction "1_1") (pintype "passive"))
      (node (ref "C22") (pin "1") (pinfunction "1_1") (pintype "passive"))
      (node (ref "C23") (pin "1") (pinfunction "1_1") (pintype "passive"))
      (node (ref "C24") (pin "1") (pinfunction "1_1") (pintype "passive"))
      (node (ref "C25") (pin "1") (pinfunction "1_1") (pintype "passive"))
      (node (ref "C27") (pin "1") (pinfunction "1_1") (pintype "passive"))
      (node (ref "C28") (pin "1") (pinfunction "1_1") (pintype "passive"))
      (node (ref "C29") (pin "1") (pinfunction "1_1") (pintype "passive"))
      (node (ref "C30") (pin "1") (pinfunction "1_1") (pintype "passive"))
      (node (ref "C31") (pin "1") (pinfunction "1_1") (pintype "passive"))
      (node (ref "C32") (pin "1") (pinfunction "1_1") (pintype "passive"))
      (node (ref "C35") (pin "1") (pinfunction "1_1") (pintype "passive"))
      (node (ref "C36") (pin "1") (pinfunction "1_1") (pintype "passive"))
      (node (ref "C37") (pin "1") (pinfunction "1_1") (pintype "passive"))
      (node (ref "C38") (pin "1") (pinfunction "1_1") (pintype "passive"))
      (node (ref "C5") (pin "1") (pinfunction "1_1") (pintype "passive"))
      (node (ref "C6") (pin "2") (pinfunction "2_2") (pintype "passive"))
      (node (ref "C7") (pin "1") (pinfunction "1_1") (pintype "passive"))
      (node (ref "C8") (pin "1") (pinfunction "1_1") (pintype "passive"))
      (node (ref "C9") (pin "1") (pinfunction "1_1") (pintype "passive"))
      (node (ref "D6") (pin "K") (pinfunction "K_K") (pintype "passive"))
      (node (ref "D7") (pin "K") (pinfunction "K_K") (pintype "passive"))
      (node (ref "D8") (pin "K") (pinfunction "K_K") (pintype "passive"))
      (node (ref "D9") (pin "K") (pinfunction "K_K") (pintype "passive"))
      (node (ref "J7") (pin "2") (pinfunction "2_2") (pintype "passive"))
      (node (ref "J7") (pin "3") (pinfunction "3_3") (pintype "passive"))
      (node (ref "R14") (pin "1") (pinfunction "1_1") (pintype "passive"))
      (node (ref "T1") (pin "2") (pinfunction "GND_2") (pintype "passive"))
      (node (ref "T1") (pin "5") (pinfunction "5_5") (pintype "passive"))
      (node (ref "U3") (pin "22") (pinfunction "FORCEON_22") (pintype "passive"))
      (node (ref "U3") (pin "32") (pinfunction "VSSIO_32") (pintype "passive"))
      (node (ref "U3") (pin "43") (pinfunction "VSSIO_43") (pintype "passive"))
      (node (ref "U3") (pin "46") (pinfunction "TESTMODE_46") (pintype "passive"))
      (node (ref "U3") (pin "49") (pinfunction "GND_49") (pintype "passive"))
    )
    (net (code "30") (name "Net-(C8-Pad2)") (class "Default")
      (node (ref "C8") (pin "2") (pinfunction "2_2") (pintype "passive"))
      (node (ref "U3") (pin "31") (pinfunction "VDDIO_31") (pintype "passive"))
    )
    (net (code "31") (name "Net-(C9-Pad2)") (class "Default")
      (node (ref "C9") (pin "2") (pinfunction "2_2") (pintype "passive"))
      (node (ref "U3") (pin "42") (pinfunction "VDDIO_42") (pintype "passive"))
    )
    (net (code "32") (name "Net-(C15-Pad2)") (class "Default")
      (node (ref "C15") (pin "2") (pinfunction "2_2") (pintype "passive"))
      (node (ref "R10") (pin "2") (pinfunction "2_2") (pintype "passive"))
    )
    (net (code "33") (name "Net-(C19-Pad2)") (class "Default")
      (node (ref "C19") (pin "2") (pinfunction "2_2") (pintype "passive"))
      (node (ref "R12") (pin "1") (pinfunction "1_1") (pintype "passive"))
    )
    (net (code "34") (name "Net-(C33-Pad1)") (class "Default")
      (node (ref "C33") (pin "1") (pinfunction "1_1") (pintype "passive"))
      (node (ref "T1") (pin "4") (pinfunction "4_4") (pintype "passive"))
    )
    (net (code "35") (name "Net-(C34-Pad1)") (class "Default")
      (node (ref "C34") (pin "1") (pinfunction "1_1") (pintype "passive"))
      (node (ref "T1") (pin "3") (pinfunction "3_3") (pintype "passive"))
    )
    (net (code "36") (name "Net-(D6-PadA)") (class "Default")
      (node (ref "D6") (pin "A") (pinfunction "A_A") (pintype "passive"))
      (node (ref "R8") (pin "1") (pinfunction "1_1") (pintype "passive"))
    )
    (net (code "37") (name "Net-(D7-PadA)") (class "Default")
      (node (ref "D7") (pin "A") (pinfunction "A_A") (pintype "passive"))
      (node (ref "R9") (pin "1") (pinfunction "1_1") (pintype "passive"))
    )
    (net (code "38") (name "Net-(D8-PadA)") (class "Default")
      (node (ref "D8") (pin "A") (pinfunction "A_A") (pintype "passive"))
      (node (ref "R11") (pin "1") (pinfunction "1_1") (pintype "passive"))
    )
    (net (code "39") (name "Net-(D9-PadA)") (class "Default")
      (node (ref "D9") (pin "A") (pinfunction "A_A") (pintype "passive"))
      (node (ref "R13") (pin "1") (pinfunction "1_1") (pintype "passive"))
    )
    (net (code "40") (name "Net-(J7-Pad1)") (class "Default")
      (node (ref "J7") (pin "1") (pinfunction "1_1") (pintype "passive"))
      (node (ref "T1") (pin "1") (pinfunction "1_1") (pintype "passive"))
    )
    (net (code "41") (name "Net-(U3-CLKTUNE)") (class "Default")
      (node (ref "C16") (pin "1") (pinfunction "1_1") (pintype "passive"))
      (node (ref "R10") (pin "1") (pinfunction "1_1") (pintype "passive"))
      (node (ref "U3") (pin "8") (pinfunction "CLKTUNE_8") (pintype "passive"))
    )
    (net (code "42") (name "Net-(U3-VCOTUNE)") (class "Default")
      (node (ref "C18") (pin "2") (pinfunction "2_2") (pintype "passive"))
      (node (ref "R12") (pin "2") (pinfunction "2_2") (pintype "passive"))
      (node (ref "U3") (pin "12") (pinfunction "VCOTUNE_12") (pintype "passive"))
    )
    (net (code "43") (name "Net-(U3-VDDDIG)") (class "Default")
      (node (ref "C14") (pin "2") (pinfunction "2_2") (pintype "passive"))
      (node (ref "C7") (pin "2") (pinfunction "2_2") (pintype "passive"))
      (node (ref "U3") (pin "20") (pinfunction "VDDREG_20") (pintype "passive"))
      (node (ref "U3") (pin "44") (pinfunction "VDDDIG_44") (pintype "passive"))
    )
    (net (code "44") (name "Net-(U3-VDDIOA)") (class "Default")
      (node (ref "C6") (pin "1") (pinfunction "1_1") (pintype "passive"))
      (node (ref "U3") (pin "28") (pinfunction "VDDIOA_28") (pintype "passive"))
    )
    (net (code "45") (name "Net-(U3-VREF)") (class "Default")
      (node (ref "R14") (pin "2") (pinfunction "2_2") (pintype "passive"))
      (node (ref "U3") (pin "5") (pinfunction "VREF_5") (pintype "passive"))
    )
    (net (code "46") (name "Net-(U3-XTAL2)") (class "Default")
      (node (ref "C32") (pin "2") (pinfunction "2_2") (pintype "passive"))
      (node (ref "U3") (pin "4") (pinfunction "XTAL2_4") (pintype "passive"))
    )
    (net (code "47") (name "unconnected-(T1-NC-Pad6)") (class "Default")
      (node (ref "T1") (pin "6") (pinfunction "NC_6") (pintype "passive+no_connect"))
    )
    (net (code "48") (name "unconnected-(U3-NC-Pad1)") (class "Default")
      (node (ref "U3") (pin "1") (pinfunction "NC_1") (pintype "passive+no_connect"))
    )
    (net (code "49") (name "unconnected-(U3-NC-Pad2)") (class "Default")
      (node (ref "U3") (pin "2") (pinfunction "NC_2") (pintype "passive+no_connect"))
    )
    (net (code "50") (name "unconnected-(U3-NC-Pad13)") (class "Default")
      (node (ref "U3") (pin "13") (pinfunction "NC_13") (pintype "passive+no_connect"))
    )
    (net (code "51") (name "unconnected-(U3-NC-Pad14)") (class "Default")
      (node (ref "U3") (pin "14") (pinfunction "NC_14") (pintype "passive+no_connect"))
    )
  )
)
